# PowerElectronicMW.net
KiCad netlist of a schematic drawn in EAGLE
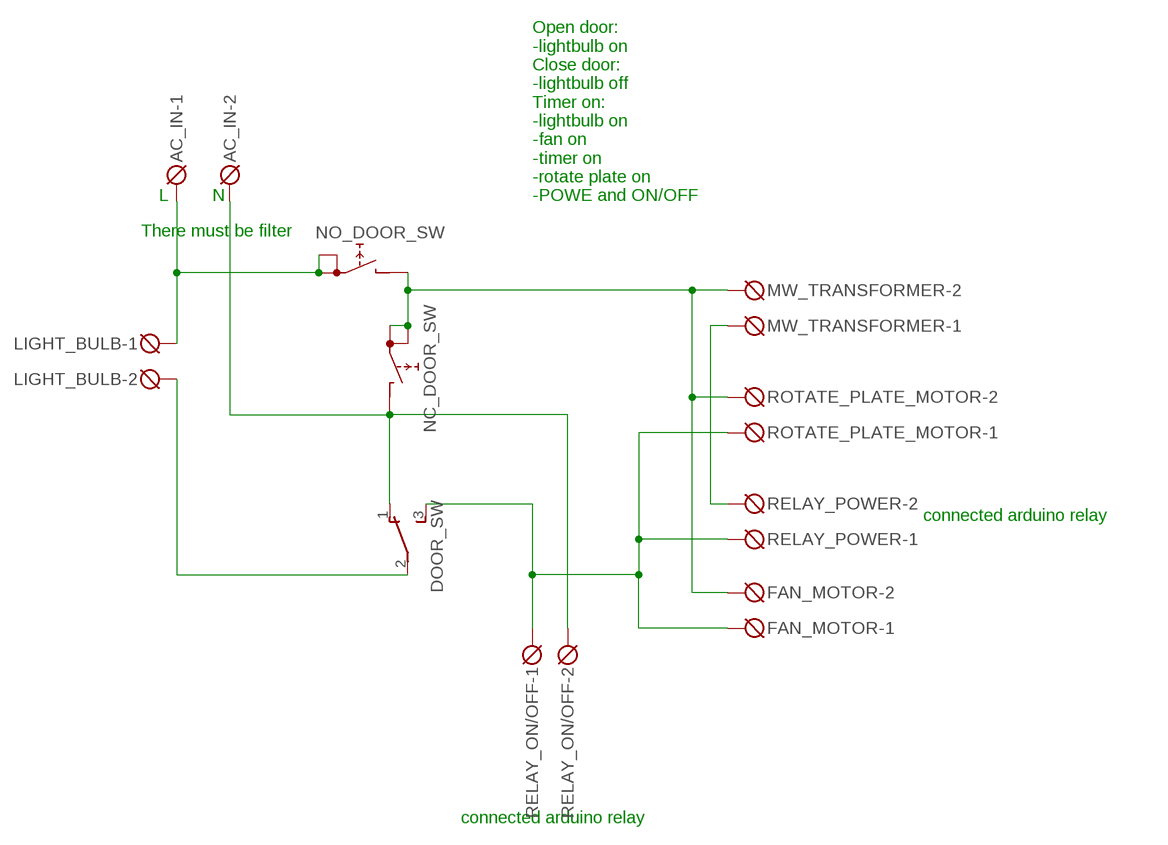
[diagram p0: schematic, sheet 1]

(export (version "E")
  (design (tool "Eeschema 10.0.6"))
  (components
    (comp (ref "AC_IN")
      (value "DG3XX-02-5.0")
      (footprint "eagle-import:DG306-5.0-02P")
      (libsource (lib "eagle-import") (part "DG3XX-02-5.0"))
    )
    (comp (ref "DOOR_SW")
      (value "TL36PO")
      (footprint "eagle-import:TL3XPO")
      (libsource (lib "eagle-import") (part "TL36PO"))
    )
    (comp (ref "FAN_MOTOR")
      (value "DG3XX-02-5.0")
      (footprint "eagle-import:DG306-5.0-02P")
      (libsource (lib "eagle-import") (part "DG3XX-02-5.0"))
    )
    (comp (ref "LIGHT_BULB")
      (value "DG3XX-02-5.0")
      (footprint "eagle-import:DG306-5.0-02P")
      (libsource (lib "eagle-import") (part "DG3XX-02-5.0"))
    )
    (comp (ref "MW_TRANSFORMER")
      (value "DG3XX-02-5.0")
      (footprint "eagle-import:DG306-5.0-02P")
      (libsource (lib "eagle-import") (part "DG3XX-02-5.0"))
    )
    (comp (ref "NC_DOOR_SW")
      (value "RDT1034")
      (footprint "eagle-import:RDT1034")
      (libsource (lib "eagle-import") (part "RDT1034"))
    )
    (comp (ref "NO_DOOR_SW")
      (value "RDT1034")
      (footprint "eagle-import:RDT1034")
      (libsource (lib "eagle-import") (part "RDT1034"))
    )
    (comp (ref "RELAY_ON/OFF")
      (value "DG3XX-02-5.0")
      (footprint "eagle-import:DG306-5.0-02P")
      (libsource (lib "eagle-import") (part "DG3XX-02-5.0"))
    )
    (comp (ref "RELAY_POWER")
      (value "DG3XX-02-5.0")
      (footprint "eagle-import:DG306-5.0-02P")
      (libsource (lib "eagle-import") (part "DG3XX-02-5.0"))
    )
    (comp (ref "ROTATE_PLATE_MOTOR")
      (value "DG3XX-02-5.0")
      (footprint "eagle-import:DG306-5.0-02P")
      (libsource (lib "eagle-import") (part "DG3XX-02-5.0"))
    )
  )
  (nets
    (net (code "1") (name "Net-(AC_INA-KL)") (class "Default")
      (node (ref "AC_IN") (pin "1") (pinfunction "KL_1") (pintype "passive"))
      (node (ref "LIGHT_BULB") (pin "1") (pinfunction "KL_1") (pintype "passive"))
      (node (ref "NO_DOOR_SW") (pin "A") (pinfunction "A_A") (pintype "passive"))
      (node (ref "NO_DOOR_SW") (pin "A1") (pinfunction "A1_A1") (pintype "passive"))
    )
    (net (code "2") (name "Net-(AC_INB-KL)") (class "Default")
      (node (ref "AC_IN") (pin "2") (pinfunction "KL_2") (pintype "passive"))
      (node (ref "DOOR_SW") (pin "1") (pinfunction "O_1") (pintype "passive"))
      (node (ref "NC_DOOR_SW") (pin "B") (pinfunction "B_B") (pintype "passive"))
      (node (ref "RELAY_ON/OFF") (pin "2") (pinfunction "KL_2") (pintype "passive"))
    )
    (net (code "3") (name "Net-(DOOR_SW-P)") (class "Default")
      (node (ref "DOOR_SW") (pin "2") (pinfunction "P_2") (pintype "passive"))
      (node (ref "LIGHT_BULB") (pin "2") (pinfunction "KL_2") (pintype "passive"))
    )
    (net (code "4") (name "Net-(DOOR_SW-S)") (class "Default")
      (node (ref "DOOR_SW") (pin "3") (pinfunction "S_3") (pintype "passive"))
      (node (ref "FAN_MOTOR") (pin "1") (pinfunction "KL_1") (pintype "passive"))
      (node (ref "RELAY_ON/OFF") (pin "1") (pinfunction "KL_1") (pintype "passive"))
      (node (ref "RELAY_POWER") (pin "1") (pinfunction "KL_1") (pintype "passive"))
      (node (ref "ROTATE_PLATE_MOTOR") (pin "1") (pinfunction "KL_1") (pintype "passive"))
    )
    (net (code "5") (name "Net-(FAN_MOTORB-KL)") (class "Default")
      (node (ref "FAN_MOTOR") (pin "2") (pinfunction "KL_2") (pintype "passive"))
      (node (ref "MW_TRANSFORMER") (pin "2") (pinfunction "KL_2") (pintype "passive"))
      (node (ref "NC_DOOR_SW") (pin "A") (pinfunction "A_A") (pintype "passive"))
      (node (ref "NC_DOOR_SW") (pin "A1") (pinfunction "A1_A1") (pintype "passive"))
      (node (ref "NO_DOOR_SW") (pin "B") (pinfunction "B_B") (pintype "passive"))
      (node (ref "ROTATE_PLATE_MOTOR") (pin "2") (pinfunction "KL_2") (pintype "passive"))
    )
    (net (code "6") (name "Net-(MW_TRANSFORMERA-KL)") (class "Default")
      (node (ref "MW_TRANSFORMER") (pin "1") (pinfunction "KL_1") (pintype "passive"))
      (node (ref "RELAY_POWER") (pin "2") (pinfunction "KL_2") (pintype "passive"))
    )
  )
)
